# buttons.net
KiCad netlist of a schematic drawn in EAGLE
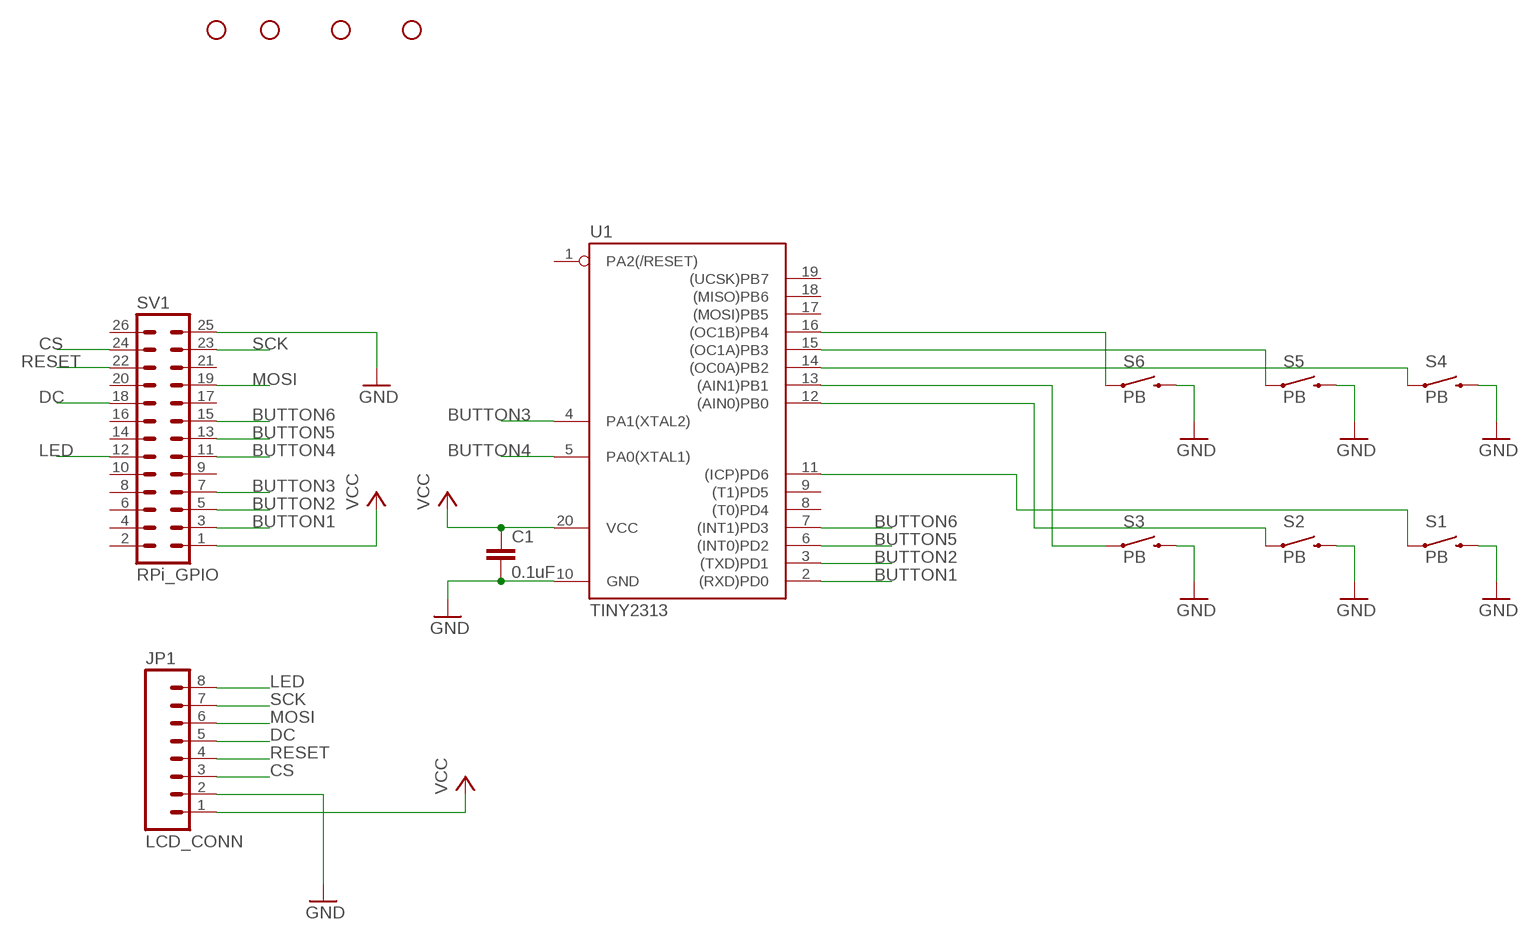
[diagram p0: schematic, sheet 1]

(export (version "E")
  (design (tool "Eeschema 10.0.6"))
  (components
    (comp (ref "C1")
      (value "0.1uF")
      (footprint "eagle-import:C2.5-2")
      (libsource (lib "eagle-import") (part "C2.5/2"))
    )
    (comp (ref "JP1")
      (value "LCD_CONN")
      (footprint "eagle-import:1X08")
      (libsource (lib "eagle-import") (part "M081X08"))
    )
    (comp (ref "S1")
      (value "PB")
      (footprint "eagle-import:TACTILE-PTH-12MM")
      (libsource (lib "eagle-import") (part "SWITCH-MOMENTARY-212MM"))
    )
    (comp (ref "S2")
      (value "PB")
      (footprint "eagle-import:TACTILE-PTH-12MM")
      (libsource (lib "eagle-import") (part "SWITCH-MOMENTARY-212MM"))
    )
    (comp (ref "S3")
      (value "PB")
      (footprint "eagle-import:TACTILE-PTH-12MM")
      (libsource (lib "eagle-import") (part "SWITCH-MOMENTARY-212MM"))
    )
    (comp (ref "S4")
      (value "PB")
      (footprint "eagle-import:TACTILE-PTH-12MM")
      (libsource (lib "eagle-import") (part "SWITCH-MOMENTARY-212MM"))
    )
    (comp (ref "S5")
      (value "PB")
      (footprint "eagle-import:TACTILE-PTH-12MM")
      (libsource (lib "eagle-import") (part "SWITCH-MOMENTARY-212MM"))
    )
    (comp (ref "S6")
      (value "PB")
      (footprint "eagle-import:TACTILE-PTH-12MM")
      (libsource (lib "eagle-import") (part "SWITCH-MOMENTARY-212MM"))
    )
    (comp (ref "STANDOFF1")
      (value "STAND-OFF")
      (footprint "eagle-import:STAND-OFF")
      (libsource (lib "eagle-import") (part "STAND-OFF"))
    )
    (comp (ref "STANDOFF2")
      (value "STAND-OFF")
      (footprint "eagle-import:STAND-OFF")
      (libsource (lib "eagle-import") (part "STAND-OFF"))
    )
    (comp (ref "STANDOFF3")
      (value "STAND-OFF")
      (footprint "eagle-import:STAND-OFF")
      (libsource (lib "eagle-import") (part "STAND-OFF"))
    )
    (comp (ref "STANDOFF4")
      (value "STAND-OFF")
      (footprint "eagle-import:STAND-OFF")
      (libsource (lib "eagle-import") (part "STAND-OFF"))
    )
    (comp (ref "SV1")
      (value "RPi_GPIO")
      (footprint "eagle-import:ML26")
      (libsource (lib "eagle-import") (part "ML26"))
    )
    (comp (ref "U1")
      (value "TINY2313")
      (footprint "eagle-import:DIL20")
      (libsource (lib "eagle-import") (part "TINY2313-P"))
    )
  )
  (nets
    (net (code "1") (name "/BUTTON1") (class "Default")
      (node (ref "SV1") (pin "3") (pinfunction "3_3") (pintype "passive"))
      (node (ref "U1") (pin "2") (pinfunction "(RXD)PD0_2") (pintype "bidirectional"))
    )
    (net (code "2") (name "/BUTTON2") (class "Default")
      (node (ref "SV1") (pin "5") (pinfunction "5_5") (pintype "passive"))
      (node (ref "U1") (pin "3") (pinfunction "(TXD)PD1_3") (pintype "bidirectional"))
    )
    (net (code "3") (name "/BUTTON3") (class "Default")
      (node (ref "SV1") (pin "7") (pinfunction "7_7") (pintype "passive"))
      (node (ref "U1") (pin "4") (pinfunction "PA1(XTAL2)_4") (pintype "bidirectional"))
    )
    (net (code "4") (name "/BUTTON4") (class "Default")
      (node (ref "SV1") (pin "11") (pinfunction "11_11") (pintype "passive"))
      (node (ref "U1") (pin "5") (pinfunction "PA0(XTAL1)_5") (pintype "bidirectional"))
    )
    (net (code "5") (name "/BUTTON5") (class "Default")
      (node (ref "SV1") (pin "13") (pinfunction "13_13") (pintype "passive"))
      (node (ref "U1") (pin "6") (pinfunction "(INT0)PD2_6") (pintype "bidirectional"))
    )
    (net (code "6") (name "/BUTTON6") (class "Default")
      (node (ref "SV1") (pin "15") (pinfunction "15_15") (pintype "passive"))
      (node (ref "U1") (pin "7") (pinfunction "(INT1)PD3_7") (pintype "bidirectional"))
    )
    (net (code "7") (name "/CS") (class "Default")
      (node (ref "JP1") (pin "3") (pinfunction "3_3") (pintype "passive"))
      (node (ref "SV1") (pin "24") (pinfunction "24_24") (pintype "passive"))
    )
    (net (code "8") (name "/DC") (class "Default")
      (node (ref "JP1") (pin "5") (pinfunction "5_5") (pintype "passive"))
      (node (ref "SV1") (pin "18") (pinfunction "18_18") (pintype "passive"))
    )
    (net (code "9") (name "/LED") (class "Default")
      (node (ref "JP1") (pin "8") (pinfunction "8_8") (pintype "passive"))
      (node (ref "SV1") (pin "12") (pinfunction "12_12") (pintype "passive"))
    )
    (net (code "10") (name "/MOSI") (class "Default")
      (node (ref "JP1") (pin "6") (pinfunction "6_6") (pintype "passive"))
      (node (ref "SV1") (pin "19") (pinfunction "19_19") (pintype "passive"))
    )
    (net (code "11") (name "/RESET") (class "Default")
      (node (ref "JP1") (pin "4") (pinfunction "4_4") (pintype "passive"))
      (node (ref "SV1") (pin "22") (pinfunction "22_22") (pintype "passive"))
    )
    (net (code "12") (name "/SCK") (class "Default")
      (node (ref "JP1") (pin "7") (pinfunction "7_7") (pintype "passive"))
      (node (ref "SV1") (pin "23") (pinfunction "23_23") (pintype "passive"))
    )
    (net (code "13") (name "GND") (class "Default")
      (node (ref "C1") (pin "2") (pinfunction "2_2") (pintype "passive"))
      (node (ref "JP1") (pin "2") (pinfunction "2_2") (pintype "passive"))
      (node (ref "S1") (pin "3") (pinfunction "2_3") (pintype "passive"))
      (node (ref "S2") (pin "3") (pinfunction "2_3") (pintype "passive"))
      (node (ref "S3") (pin "3") (pinfunction "2_3") (pintype "passive"))
      (node (ref "S4") (pin "3") (pinfunction "2_3") (pintype "passive"))
      (node (ref "S5") (pin "3") (pinfunction "2_3") (pintype "passive"))
      (node (ref "S6") (pin "3") (pinfunction "2_3") (pintype "passive"))
      (node (ref "SV1") (pin "25") (pinfunction "25_25") (pintype "passive"))
      (node (ref "U1") (pin "10") (pinfunction "GND_10") (pintype "power_in"))
    )
    (net (code "14") (name "Net-(U1-(AIN0)PB0)") (class "Default")
      (node (ref "S2") (pin "1") (pinfunction "1_1") (pintype "passive"))
      (node (ref "U1") (pin "12") (pinfunction "(AIN0)PB0_12") (pintype "bidirectional"))
    )
    (net (code "15") (name "Net-(U1-(AIN1)PB1)") (class "Default")
      (node (ref "S3") (pin "1") (pinfunction "1_1") (pintype "passive"))
      (node (ref "U1") (pin "13") (pinfunction "(AIN1)PB1_13") (pintype "bidirectional"))
    )
    (net (code "16") (name "Net-(U1-(ICP)PD6)") (class "Default")
      (node (ref "S1") (pin "1") (pinfunction "1_1") (pintype "passive"))
      (node (ref "U1") (pin "11") (pinfunction "(ICP)PD6_11") (pintype "bidirectional"))
    )
    (net (code "17") (name "Net-(U1-(OC0A)PB2)") (class "Default")
      (node (ref "S4") (pin "1") (pinfunction "1_1") (pintype "passive"))
      (node (ref "U1") (pin "14") (pinfunction "(OC0A)PB2_14") (pintype "bidirectional"))
    )
    (net (code "18") (name "Net-(U1-(OC1A)PB3)") (class "Default")
      (node (ref "S5") (pin "1") (pinfunction "1_1") (pintype "passive"))
      (node (ref "U1") (pin "15") (pinfunction "(OC1A)PB3_15") (pintype "bidirectional"))
    )
    (net (code "19") (name "Net-(U1-(OC1B)PB4)") (class "Default")
      (node (ref "S6") (pin "1") (pinfunction "1_1") (pintype "passive"))
      (node (ref "U1") (pin "16") (pinfunction "(OC1B)PB4_16") (pintype "bidirectional"))
    )
    (net (code "20") (name "VCC") (class "Default")
      (node (ref "C1") (pin "1") (pinfunction "1_1") (pintype "passive"))
      (node (ref "JP1") (pin "1") (pinfunction "1_1") (pintype "passive"))
      (node (ref "SV1") (pin "1") (pinfunction "1_1") (pintype "passive"))
      (node (ref "U1") (pin "20") (pinfunction "VCC_20") (pintype "power_in"))
    )
    (net (code "21") (name "unconnected-(SV1-Pad2)") (class "Default")
      (node (ref "SV1") (pin "2") (pinfunction "2_2") (pintype "passive"))
    )
    (net (code "22") (name "unconnected-(SV1-Pad4)") (class "Default")
      (node (ref "SV1") (pin "4") (pinfunction "4_4") (pintype "passive"))
    )
    (net (code "23") (name "unconnected-(SV1-Pad6)") (class "Default")
      (node (ref "SV1") (pin "6") (pinfunction "6_6") (pintype "passive"))
    )
    (net (code "24") (name "unconnected-(SV1-Pad8)") (class "Default")
      (node (ref "SV1") (pin "8") (pinfunction "8_8") (pintype "passive"))
    )
    (net (code "25") (name "unconnected-(SV1-Pad9)") (class "Default")
      (node (ref "SV1") (pin "9") (pinfunction "9_9") (pintype "passive"))
    )
    (net (code "26") (name "unconnected-(SV1-Pad10)") (class "Default")
      (node (ref "SV1") (pin "10") (pinfunction "10_10") (pintype "passive"))
    )
    (net (code "27") (name "unconnected-(SV1-Pad14)") (class "Default")
      (node (ref "SV1") (pin "14") (pinfunction "14_14") (pintype "passive"))
    )
    (net (code "28") (name "unconnected-(SV1-Pad16)") (class "Default")
      (node (ref "SV1") (pin "16") (pinfunction "16_16") (pintype "passive"))
    )
    (net (code "29") (name "unconnected-(SV1-Pad17)") (class "Default")
      (node (ref "SV1") (pin "17") (pinfunction "17_17") (pintype "passive"))
    )
    (net (code "30") (name "unconnected-(SV1-Pad20)") (class "Default")
      (node (ref "SV1") (pin "20") (pinfunction "20_20") (pintype "passive"))
    )
    (net (code "31") (name "unconnected-(SV1-Pad21)") (class "Default")
      (node (ref "SV1") (pin "21") (pinfunction "21_21") (pintype "passive"))
    )
    (net (code "32") (name "unconnected-(SV1-Pad26)") (class "Default")
      (node (ref "SV1") (pin "26") (pinfunction "26_26") (pintype "passive"))
    )
    (net (code "33") (name "unconnected-(U1-(MISO)PB6-Pad18)") (class "Default")
      (node (ref "U1") (pin "18") (pinfunction "(MISO)PB6_18") (pintype "bidirectional"))
    )
    (net (code "34") (name "unconnected-(U1-(MOSI)PB5-Pad17)") (class "Default")
      (node (ref "U1") (pin "17") (pinfunction "(MOSI)PB5_17") (pintype "bidirectional"))
    )
    (net (code "35") (name "unconnected-(U1-(T0)PD4-Pad8)") (class "Default")
      (node (ref "U1") (pin "8") (pinfunction "(T0)PD4_8") (pintype "bidirectional"))
    )
    (net (code "36") (name "unconnected-(U1-(T1)PD5-Pad9)") (class "Default")
      (node (ref "U1") (pin "9") (pinfunction "(T1)PD5_9") (pintype "bidirectional"))
    )
    (net (code "37") (name "unconnected-(U1-(UCSK)PB7-Pad19)") (class "Default")
      (node (ref "U1") (pin "19") (pinfunction "(UCSK)PB7_19") (pintype "bidirectional"))
    )
    (net (code "38") (name "unconnected-(U1-PA2({slash}RESET)-Pad1)") (class "Default")
      (node (ref "U1") (pin "1") (pinfunction "PA2(/RESET)_1") (pintype "input"))
    )
  )
)
